# Display.net
KiCad netlist of a schematic drawn in Altium Designer
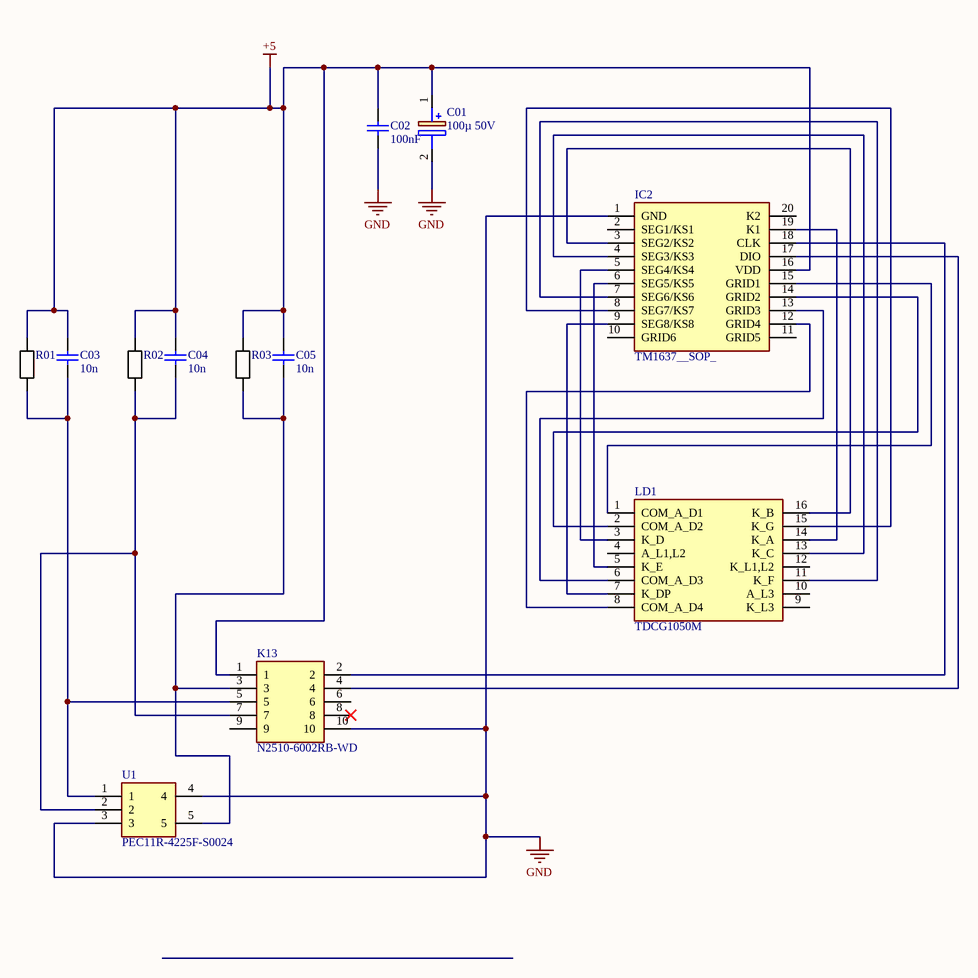
[diagram p0: Display.SchDoc]

(export (version "E")
  (design (tool "Eeschema 10.0.6"))
  (components
    (comp (ref "C01")
      (value "100µ 50V")
      (footprint "SamacSys:CAPPRD500W65D1025H1250")
      (description "Capacitor Polarised")
      (fields
        (field (name "MANUFACTURER_PART_NUMBER") "B41851A6227M000")
        (field (name "MOUSER PART NUMBER") "871-B41851A6227M000")
      )
      (libsource (lib "*") (part "B41851A6227M000"))
    )
    (comp (ref "C02")
      (value "100nF")
      (footprint "*CAPC2012X94N")
      (fields
        (field (name "PART NUMBER") "02015A270JAT2A")
        (field (name "MANUFACTURER") "AVX Interconnect / Elco")
      )
      (libsource (lib "Schlib1") (part "CAP"))
    )
    (comp (ref "C03")
      (value "10n")
      (footprint "LIBRARYSOURCE=Vault")
      (fields
        (field (name "PART NUMBER") "02015A270JAT2A")
        (field (name "MANUFACTURER") "AVX Interconnect / Elco")
      )
      (libsource (lib "Schlib1") (part "CAP"))
    )
    (comp (ref "C04")
      (value "10n")
      (footprint "LIBRARYSOURCE=Vault")
      (fields
        (field (name "PART NUMBER") "02015A270JAT2A")
        (field (name "MANUFACTURER") "AVX Interconnect / Elco")
      )
      (libsource (lib "Schlib1") (part "CAP"))
    )
    (comp (ref "C05")
      (value "10n")
      (footprint "LIBRARYSOURCE=Vault")
      (fields
        (field (name "PART NUMBER") "02015A270JAT2A")
        (field (name "MANUFACTURER") "AVX Interconnect / Elco")
      )
      (libsource (lib "Schlib1") (part "CAP"))
    )
    (comp (ref "IC2")
      (value "TM1637__SOP_")
      (footprint "SamacSys:SOIC127P1045X280-20N")
      (description "Integrated Circuit")
      (fields (field (name "MANUFACTURER_PART_NUMBER") "TM1637 (SOP)"))
      (libsource (lib "Schlib1") (part "TM1637__SOP_"))
    )
    (comp (ref "K13")
      (value "N2510-6002RB-WD")
      (footprint "SamacSys:N25106002RBWD")
      (description "Connector")
      (fields (field (name "MOUSER PART NUMBER") "517-N2510-6002RB-WD"))
      (libsource (lib "Schlib1") (part "N2510-6002RB-WD"))
    )
    (comp (ref "LD1")
      (value "TDCG1050M")
      (footprint "SamacSys:DIPS1016W75P254L4020H725Q16N")
      (description "Display")
      (fields (field (name "MOUSER PART NUMBER") "78-TDCG1050"))
      (libsource (lib "*") (part "TDCG1050M"))
    )
    (comp (ref "R01")
      (value "CRCW08050000Z0EA")
      (footprint "RESC2012X65N")
      (fields (field (name "MANUFACTURER") "Vishay Dale"))
      (libsource (lib "Schlib1") (part "RES"))
    )
    (comp (ref "R02")
      (value "CRCW08050000Z0EA")
      (footprint "RESC2012X65N")
      (fields (field (name "MANUFACTURER") "Vishay Dale"))
      (libsource (lib "Schlib1") (part "RES"))
    )
    (comp (ref "R03")
      (value "CRCW08050000Z0EA")
      (footprint "RESC2012X65N")
      (fields (field (name "MANUFACTURER") "Vishay Dale"))
      (libsource (lib "Schlib1") (part "RES"))
    )
    (comp (ref "U1")
      (value "PEC11R-4225F-S0024")
      (footprint "SamacSys:PEC12R-4XXXF-SXXXX_1")
      (description "Undefined or Miscellaneous")
      (fields (field (name "MOUSER PART NUMBER") "652-PEC11R-4225F-S24"))
      (libsource (lib "Schlib1") (part "PEC11R-4225F-S0024"))
    )
  )
  (nets
    (net (code "1") (name "+5") (class "Default")
      (node (ref "C01") (pin "1") (pinfunction "+_1") (pintype "passive"))
      (node (ref "C02") (pin "2") (pinfunction "2_2") (pintype "passive"))
      (node (ref "C03") (pin "2") (pinfunction "2_2") (pintype "passive"))
      (node (ref "C04") (pin "2") (pinfunction "2_2") (pintype "passive"))
      (node (ref "C05") (pin "2") (pinfunction "2_2") (pintype "passive"))
      (node (ref "IC2") (pin "16") (pinfunction "VDD_16") (pintype "passive"))
      (node (ref "K13") (pin "1") (pinfunction "1_1") (pintype "passive"))
      (node (ref "R01") (pin "2") (pinfunction "2_2") (pintype "passive"))
      (node (ref "R02") (pin "2") (pinfunction "2_2") (pintype "passive"))
      (node (ref "R03") (pin "2") (pinfunction "2_2") (pintype "passive"))
    )
    (net (code "2") (name "GND") (class "Default")
      (node (ref "C01") (pin "2") (pinfunction "-_2") (pintype "passive"))
      (node (ref "C02") (pin "1") (pinfunction "1_1") (pintype "passive"))
      (node (ref "IC2") (pin "1") (pinfunction "GND_1") (pintype "passive"))
      (node (ref "K13") (pin "10") (pinfunction "10_10") (pintype "passive"))
      (node (ref "U1") (pin "3") (pinfunction "3_3") (pintype "passive"))
      (node (ref "U1") (pin "4") (pinfunction "4_4") (pintype "passive"))
    )
    (net (code "3") (name "Net-(C03-Pad1)") (class "Default")
      (node (ref "C03") (pin "1") (pinfunction "1_1") (pintype "passive"))
      (node (ref "K13") (pin "5") (pinfunction "5_5") (pintype "passive"))
      (node (ref "R01") (pin "1") (pinfunction "1_1") (pintype "passive"))
      (node (ref "U1") (pin "1") (pinfunction "1_1") (pintype "passive"))
    )
    (net (code "4") (name "Net-(C04-Pad1)") (class "Default")
      (node (ref "C04") (pin "1") (pinfunction "1_1") (pintype "passive"))
      (node (ref "K13") (pin "7") (pinfunction "7_7") (pintype "passive"))
      (node (ref "R02") (pin "1") (pinfunction "1_1") (pintype "passive"))
      (node (ref "U1") (pin "2") (pinfunction "2_2") (pintype "passive"))
    )
    (net (code "5") (name "Net-(C05-Pad1)") (class "Default")
      (node (ref "C05") (pin "1") (pinfunction "1_1") (pintype "passive"))
      (node (ref "K13") (pin "3") (pinfunction "3_3") (pintype "passive"))
      (node (ref "R03") (pin "1") (pinfunction "1_1") (pintype "passive"))
      (node (ref "U1") (pin "5") (pinfunction "5_5") (pintype "passive"))
    )
    (net (code "6") (name "Net-(IC2-CLK)") (class "Default")
      (node (ref "IC2") (pin "18") (pinfunction "CLK_18") (pintype "passive"))
      (node (ref "K13") (pin "2") (pinfunction "2_2") (pintype "passive"))
    )
    (net (code "7") (name "Net-(IC2-DIO)") (class "Default")
      (node (ref "IC2") (pin "17") (pinfunction "DIO_17") (pintype "passive"))
      (node (ref "K13") (pin "4") (pinfunction "4_4") (pintype "passive"))
    )
    (net (code "8") (name "Net-(IC2-GRID1)") (class "Default")
      (node (ref "IC2") (pin "15") (pinfunction "GRID1_15") (pintype "passive"))
      (node (ref "LD1") (pin "1") (pinfunction "COM_A_D1_1") (pintype "passive"))
    )
    (net (code "9") (name "Net-(IC2-GRID2)") (class "Default")
      (node (ref "IC2") (pin "14") (pinfunction "GRID2_14") (pintype "passive"))
      (node (ref "LD1") (pin "2") (pinfunction "COM_A_D2_2") (pintype "passive"))
    )
    (net (code "10") (name "Net-(IC2-GRID3)") (class "Default")
      (node (ref "IC2") (pin "13") (pinfunction "GRID3_13") (pintype "passive"))
      (node (ref "LD1") (pin "6") (pinfunction "COM_A_D3_6") (pintype "passive"))
    )
    (net (code "11") (name "Net-(IC2-GRID4)") (class "Default")
      (node (ref "IC2") (pin "12") (pinfunction "GRID4_12") (pintype "passive"))
      (node (ref "LD1") (pin "8") (pinfunction "COM_A_D4_8") (pintype "passive"))
    )
    (net (code "12") (name "Net-(IC2-K1)") (class "Default")
      (node (ref "IC2") (pin "19") (pinfunction "K1_19") (pintype "passive"))
      (node (ref "LD1") (pin "14") (pinfunction "K_A_14") (pintype "passive"))
    )
    (net (code "13") (name "Net-(IC2-SEG2{slash}KS2)") (class "Default")
      (node (ref "IC2") (pin "3") (pinfunction "SEG2/KS2_3") (pintype "passive"))
      (node (ref "LD1") (pin "16") (pinfunction "K_B_16") (pintype "passive"))
    )
    (net (code "14") (name "Net-(IC2-SEG3{slash}KS3)") (class "Default")
      (node (ref "IC2") (pin "4") (pinfunction "SEG3/KS3_4") (pintype "passive"))
      (node (ref "LD1") (pin "13") (pinfunction "K_C_13") (pintype "passive"))
    )
    (net (code "15") (name "Net-(IC2-SEG4{slash}KS4)") (class "Default")
      (node (ref "IC2") (pin "5") (pinfunction "SEG4/KS4_5") (pintype "passive"))
      (node (ref "LD1") (pin "3") (pinfunction "K_D_3") (pintype "passive"))
    )
    (net (code "16") (name "Net-(IC2-SEG5{slash}KS5)") (class "Default")
      (node (ref "IC2") (pin "6") (pinfunction "SEG5/KS5_6") (pintype "passive"))
      (node (ref "LD1") (pin "5") (pinfunction "K_E_5") (pintype "passive"))
    )
    (net (code "17") (name "Net-(IC2-SEG6{slash}KS6)") (class "Default")
      (node (ref "IC2") (pin "7") (pinfunction "SEG6/KS6_7") (pintype "passive"))
      (node (ref "LD1") (pin "11") (pinfunction "K_F_11") (pintype "passive"))
    )
    (net (code "18") (name "Net-(IC2-SEG7{slash}KS7)") (class "Default")
      (node (ref "IC2") (pin "8") (pinfunction "SEG7/KS7_8") (pintype "passive"))
      (node (ref "LD1") (pin "15") (pinfunction "K_G_15") (pintype "passive"))
    )
    (net (code "19") (name "Net-(IC2-SEG8{slash}KS8)") (class "Default")
      (node (ref "IC2") (pin "9") (pinfunction "SEG8/KS8_9") (pintype "passive"))
      (node (ref "LD1") (pin "7") (pinfunction "K_DP_7") (pintype "passive"))
    )
    (net (code "20") (name "unconnected-(IC2-GRID5-Pad11)") (class "Default")
      (node (ref "IC2") (pin "11") (pinfunction "GRID5_11") (pintype "passive"))
    )
    (net (code "21") (name "unconnected-(IC2-GRID6-Pad10)") (class "Default")
      (node (ref "IC2") (pin "10") (pinfunction "GRID6_10") (pintype "passive"))
    )
    (net (code "22") (name "unconnected-(IC2-K2-Pad20)") (class "Default")
      (node (ref "IC2") (pin "20") (pinfunction "K2_20") (pintype "passive"))
    )
    (net (code "23") (name "unconnected-(IC2-SEG1{slash}KS1-Pad2)") (class "Default")
      (node (ref "IC2") (pin "2") (pinfunction "SEG1/KS1_2") (pintype "passive"))
    )
    (net (code "24") (name "unconnected-(K13-Pad6)") (class "Default")
      (node (ref "K13") (pin "6") (pinfunction "6_6") (pintype "passive"))
    )
    (net (code "25") (name "unconnected-(K13-Pad8)") (class "Default")
      (node (ref "K13") (pin "8") (pinfunction "8_8") (pintype "passive+no_connect"))
    )
    (net (code "26") (name "unconnected-(K13-Pad9)") (class "Default")
      (node (ref "K13") (pin "9") (pinfunction "9_9") (pintype "passive"))
    )
    (net (code "27") (name "unconnected-(LD1-A_L1,L2-Pad4)") (class "Default")
      (node (ref "LD1") (pin "4") (pinfunction "A_L1,L2_4") (pintype "passive"))
    )
    (net (code "28") (name "unconnected-(LD1-A_L3-Pad10)") (class "Default")
      (node (ref "LD1") (pin "10") (pinfunction "A_L3_10") (pintype "passive"))
    )
    (net (code "29") (name "unconnected-(LD1-K_L1,L2-Pad12)") (class "Default")
      (node (ref "LD1") (pin "12") (pinfunction "K_L1,L2_12") (pintype "passive"))
    )
    (net (code "30") (name "unconnected-(LD1-K_L3-Pad9)") (class "Default")
      (node (ref "LD1") (pin "9") (pinfunction "K_L3_9") (pintype "passive"))
    )
  )
)
